# Evaluation_kit.net
KiCad netlist of a schematic drawn in Altium Designer
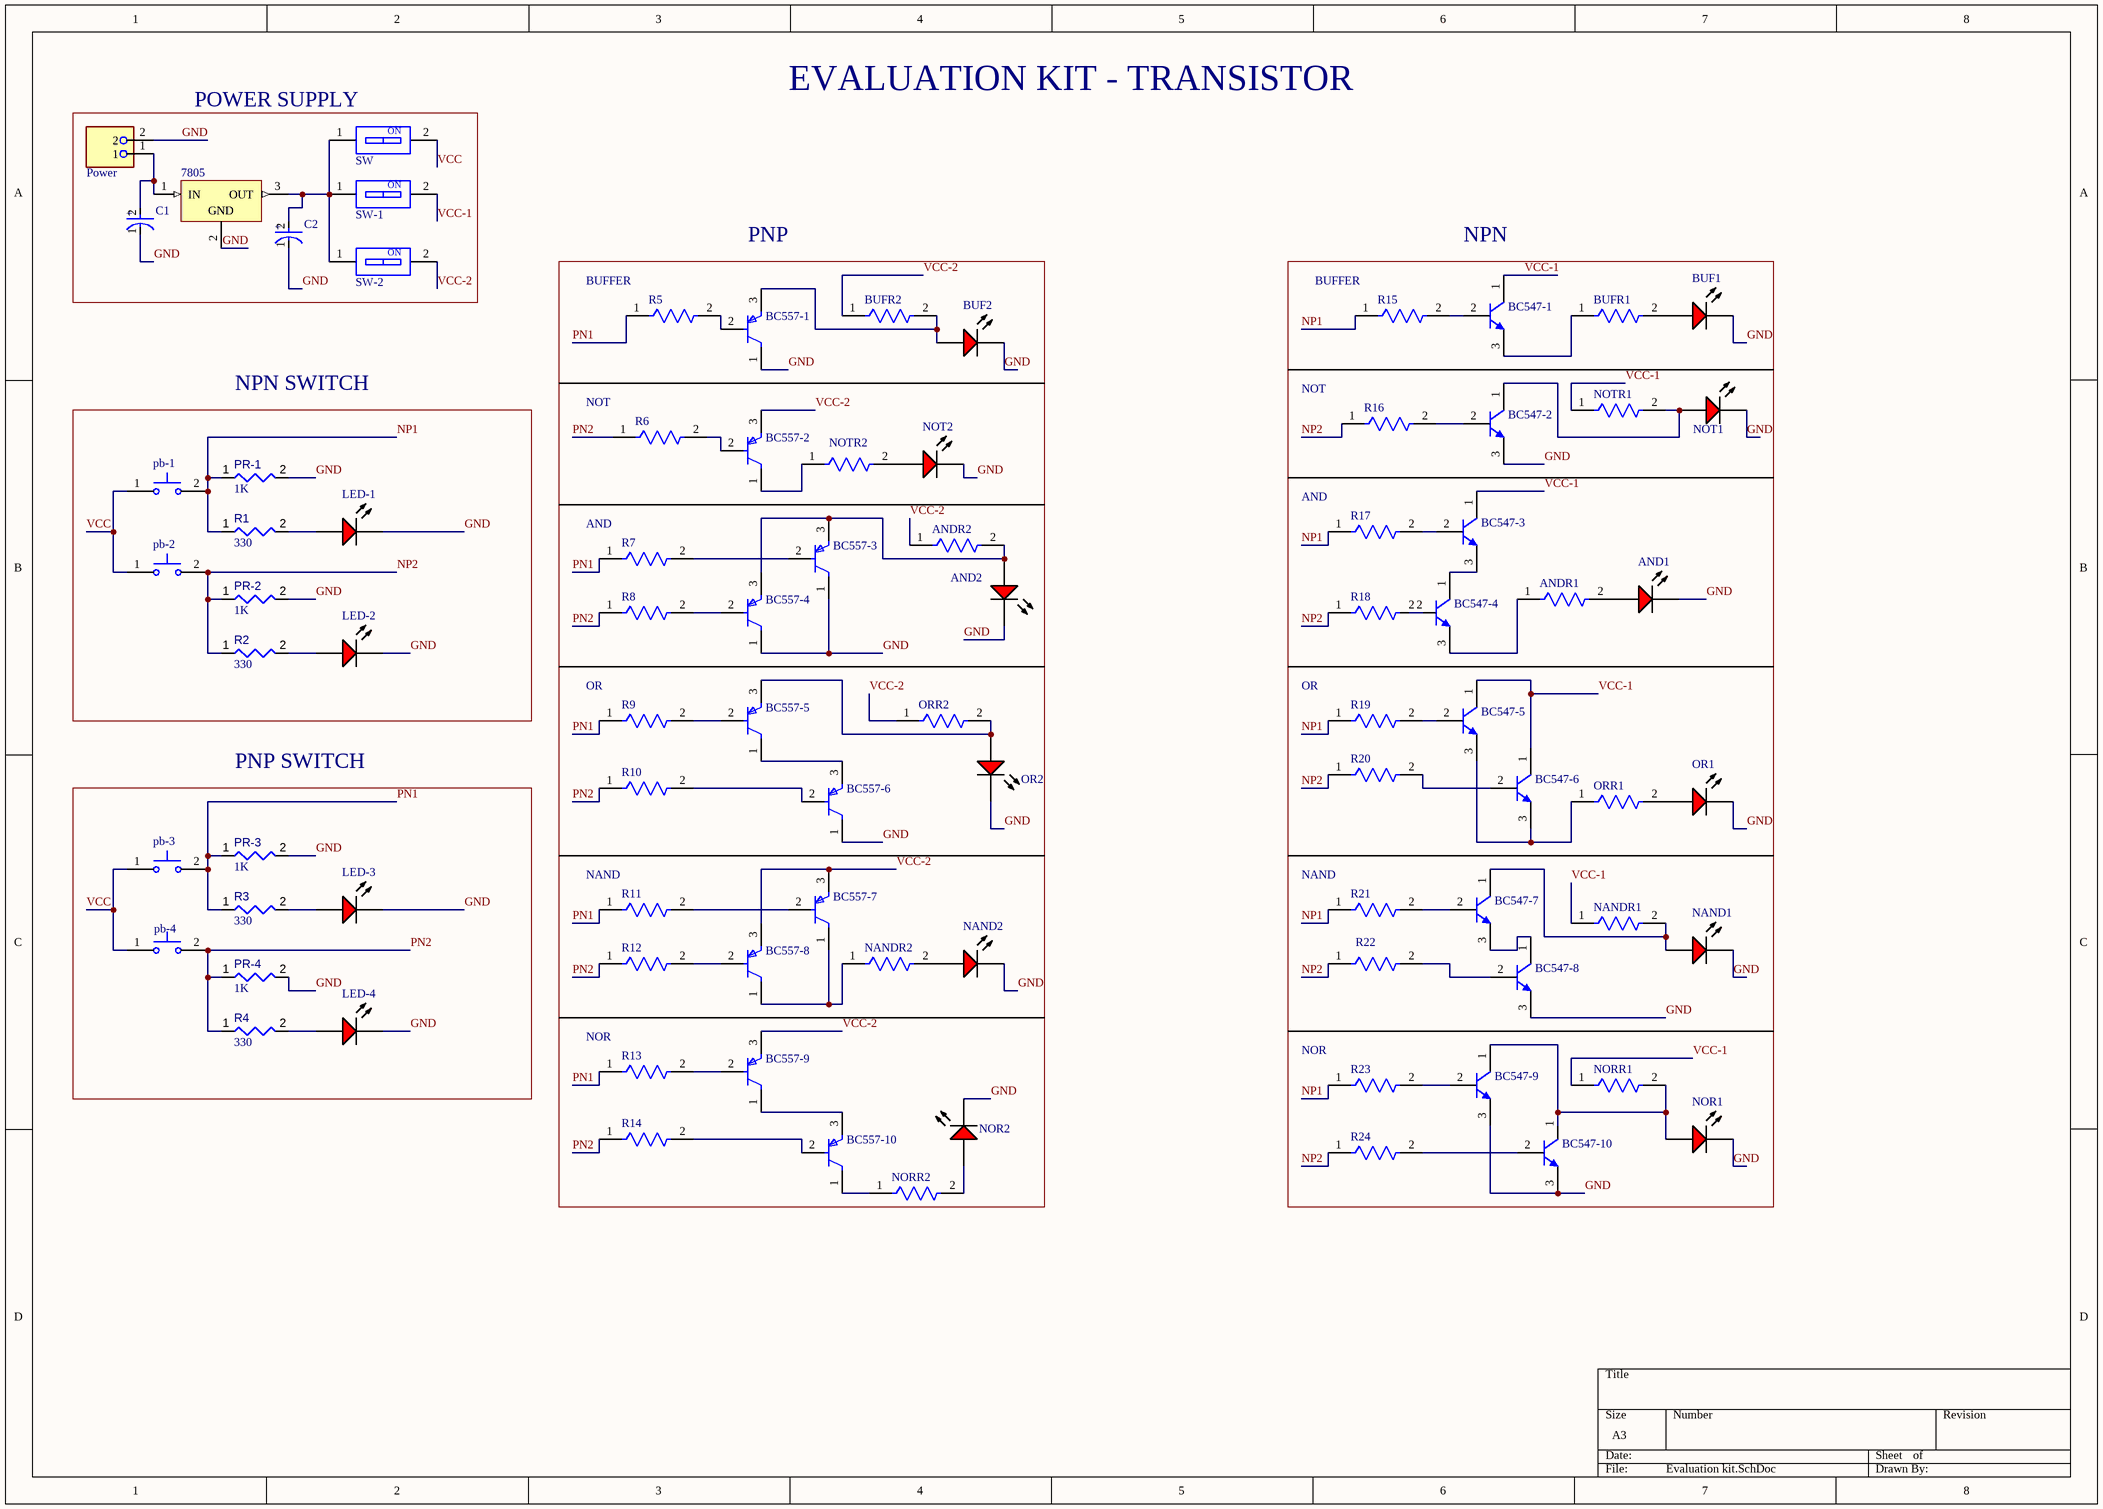
[diagram p0: Evaluation kit.SchDoc]

(export (version "E")
  (design (tool "Eeschema 10.0.6"))
  (components
    (comp (ref "7805")
      (value "LM7805ACT")
      (footprint "FAIR-TO-220-3")
      (description "Positive Voltage Regulator, 5 V, 1 A, 0 to 125 degC, 3-Pin TO-220, RoHS, Tube")
      (fields (field (name "MANUFACTURER") "Fairchild"))
      (libsource (lib "Altium Content Vault") (part "FAIR-LM7805CT-TO220-3"))
    )
    (comp (ref "AND1")
      (value "LTL-1CHE")
      (footprint "INDPR60-254-520X380X650")
      (description "LED Uni-Color Red, 100 mW, 30 mA, -55 to 100 degC, 2-Pin THD, RoHS, Bulk")
      (fields (field (name "MANUFACTURER") "Lite-On"))
      (libsource (lib "KARTHICK RAJ R") (part "LED-RED-AK-2"))
    )
    (comp (ref "AND2")
      (value "LTL-1CHE")
      (footprint "INDPR60-254-520X380X650")
      (description "LED Uni-Color Red, 100 mW, 30 mA, -55 to 100 degC, 2-Pin THD, RoHS, Bulk")
      (fields (field (name "MANUFACTURER") "Lite-On"))
      (libsource (lib "KARTHICK RAJ R") (part "LED-RED-AK-2"))
    )
    (comp (ref "ANDR1")
      (value "MBA02040C2200FC100")
      (footprint "FP-MBA0204-MFG")
      (description "RES 220 OHM 0.4W 1% AXIAL")
      (fields
        (field (name "OCTOPART") "https://octopart.com/mba02040c2200fc100-vishay-43743094")
        (field (name "MANUFACTURER") "Vishay BC Components")
      )
      (libsource (lib "Altium Content Vault") (part "1029c3af85768c4190bb7ad29bc67b5"))
    )
    (comp (ref "ANDR2")
      (value "MBA02040C2200FC100")
      (footprint "FP-MBA0204-MFG")
      (description "RES 220 OHM 0.4W 1% AXIAL")
      (fields
        (field (name "OCTOPART") "https://octopart.com/mba02040c2200fc100-vishay-43743094")
        (field (name "MANUFACTURER") "Vishay BC Components")
      )
      (libsource (lib "Altium Content Vault") (part "1029c3af85768c4190bb7ad29bc67b5"))
    )
    (comp (ref "BC547-1")
      (value "BC547BRL1G")
      (footprint "ONSC-TO-92-3-29-11_AM_BL")
      (description "Amplifier Transistor, NPN Silicon, 3-Pin TO-92, Pb-Free, Tape and Reel")
      (fields (field (name "MANUFACTURER") "On Semiconductor"))
      (libsource (lib "Altium Content Vault") (part "ONSC-NPN-C1B2E3-3"))
    )
    (comp (ref "BC547-2")
      (value "BC547BRL1G")
      (footprint "ONSC-TO-92-3-29-11_AM_BL")
      (description "Amplifier Transistor, NPN Silicon, 3-Pin TO-92, Pb-Free, Tape and Reel")
      (fields (field (name "MANUFACTURER") "On Semiconductor"))
      (libsource (lib "Altium Content Vault") (part "ONSC-NPN-C1B2E3-3"))
    )
    (comp (ref "BC547-3")
      (value "BC547BRL1G")
      (footprint "ONSC-TO-92-3-29-11_AM_BL")
      (description "Amplifier Transistor, NPN Silicon, 3-Pin TO-92, Pb-Free, Tape and Reel")
      (fields (field (name "MANUFACTURER") "On Semiconductor"))
      (libsource (lib "Altium Content Vault") (part "ONSC-NPN-C1B2E3-3"))
    )
    (comp (ref "BC547-4")
      (value "BC547BRL1G")
      (footprint "ONSC-TO-92-3-29-11_AM_BL")
      (description "Amplifier Transistor, NPN Silicon, 3-Pin TO-92, Pb-Free, Tape and Reel")
      (fields (field (name "MANUFACTURER") "On Semiconductor"))
      (libsource (lib "Altium Content Vault") (part "ONSC-NPN-C1B2E3-3"))
    )
    (comp (ref "BC547-5")
      (value "BC547BRL1G")
      (footprint "ONSC-TO-92-3-29-11_AM_BL")
      (description "Amplifier Transistor, NPN Silicon, 3-Pin TO-92, Pb-Free, Tape and Reel")
      (fields (field (name "MANUFACTURER") "On Semiconductor"))
      (libsource (lib "Altium Content Vault") (part "ONSC-NPN-C1B2E3-3"))
    )
    (comp (ref "BC547-6")
      (value "BC547BRL1G")
      (footprint "ONSC-TO-92-3-29-11_AM_BL")
      (description "Amplifier Transistor, NPN Silicon, 3-Pin TO-92, Pb-Free, Tape and Reel")
      (fields (field (name "MANUFACTURER") "On Semiconductor"))
      (libsource (lib "Altium Content Vault") (part "ONSC-NPN-C1B2E3-3"))
    )
    (comp (ref "BC547-7")
      (value "BC547BRL1G")
      (footprint "ONSC-TO-92-3-29-11_AM_BL")
      (description "Amplifier Transistor, NPN Silicon, 3-Pin TO-92, Pb-Free, Tape and Reel")
      (fields (field (name "MANUFACTURER") "On Semiconductor"))
      (libsource (lib "Altium Content Vault") (part "ONSC-NPN-C1B2E3-3"))
    )
    (comp (ref "BC547-8")
      (value "BC547BRL1G")
      (footprint "ONSC-TO-92-3-29-11_AM_BL")
      (description "Amplifier Transistor, NPN Silicon, 3-Pin TO-92, Pb-Free, Tape and Reel")
      (fields (field (name "MANUFACTURER") "On Semiconductor"))
      (libsource (lib "Altium Content Vault") (part "ONSC-NPN-C1B2E3-3"))
    )
    (comp (ref "BC547-9")
      (value "BC547BRL1G")
      (footprint "ONSC-TO-92-3-29-11_AM_BL")
      (description "Amplifier Transistor, NPN Silicon, 3-Pin TO-92, Pb-Free, Tape and Reel")
      (fields (field (name "MANUFACTURER") "On Semiconductor"))
      (libsource (lib "Altium Content Vault") (part "ONSC-NPN-C1B2E3-3"))
    )
    (comp (ref "BC547-10")
      (value "BC547BRL1G")
      (footprint "ONSC-TO-92-3-29-11_AM_BL")
      (description "Amplifier Transistor, NPN Silicon, 3-Pin TO-92, Pb-Free, Tape and Reel")
      (fields (field (name "MANUFACTURER") "On Semiconductor"))
      (libsource (lib "Altium Content Vault") (part "ONSC-NPN-C1B2E3-3"))
    )
    (comp (ref "BC557-1")
      (value "BC557BTF")
      (footprint "FP-135AR-MFG")
      (description "BC557BTF Small Signal Bipolar Transistor, 0.1A I(C), 45V V(BR)CEO, 1-Element, PNP, Silicon, TO-92")
      (libsource (lib "Altium Content Vault") (part "9e2844d3eb996af6824d2c99fe21afc"))
    )
    (comp (ref "BC557-2")
      (value "BC557BTF")
      (footprint "FP-135AR-MFG")
      (description "BC557BTF Small Signal Bipolar Transistor, 0.1A I(C), 45V V(BR)CEO, 1-Element, PNP, Silicon, TO-92")
      (libsource (lib "Altium Content Vault") (part "9e2844d3eb996af6824d2c99fe21afc"))
    )
    (comp (ref "BC557-3")
      (value "BC557BTF")
      (footprint "FP-135AR-MFG")
      (description "BC557BTF Small Signal Bipolar Transistor, 0.1A I(C), 45V V(BR)CEO, 1-Element, PNP, Silicon, TO-92")
      (libsource (lib "Altium Content Vault") (part "9e2844d3eb996af6824d2c99fe21afc"))
    )
    (comp (ref "BC557-4")
      (value "BC557BTF")
      (footprint "FP-135AR-MFG")
      (description "BC557BTF Small Signal Bipolar Transistor, 0.1A I(C), 45V V(BR)CEO, 1-Element, PNP, Silicon, TO-92")
      (libsource (lib "Altium Content Vault") (part "9e2844d3eb996af6824d2c99fe21afc"))
    )
    (comp (ref "BC557-5")
      (value "BC557BTF")
      (footprint "FP-135AR-MFG")
      (description "BC557BTF Small Signal Bipolar Transistor, 0.1A I(C), 45V V(BR)CEO, 1-Element, PNP, Silicon, TO-92")
      (libsource (lib "Altium Content Vault") (part "9e2844d3eb996af6824d2c99fe21afc"))
    )
    (comp (ref "BC557-6")
      (value "BC557BTF")
      (footprint "FP-135AR-MFG")
      (description "BC557BTF Small Signal Bipolar Transistor, 0.1A I(C), 45V V(BR)CEO, 1-Element, PNP, Silicon, TO-92")
      (libsource (lib "Altium Content Vault") (part "9e2844d3eb996af6824d2c99fe21afc"))
    )
    (comp (ref "BC557-7")
      (value "BC557BTF")
      (footprint "FP-135AR-MFG")
      (description "BC557BTF Small Signal Bipolar Transistor, 0.1A I(C), 45V V(BR)CEO, 1-Element, PNP, Silicon, TO-92")
      (libsource (lib "Altium Content Vault") (part "9e2844d3eb996af6824d2c99fe21afc"))
    )
    (comp (ref "BC557-8")
      (value "BC557BTF")
      (footprint "FP-135AR-MFG")
      (description "BC557BTF Small Signal Bipolar Transistor, 0.1A I(C), 45V V(BR)CEO, 1-Element, PNP, Silicon, TO-92")
      (libsource (lib "Altium Content Vault") (part "9e2844d3eb996af6824d2c99fe21afc"))
    )
    (comp (ref "BC557-9")
      (value "BC557BTF")
      (footprint "FP-135AR-MFG")
      (description "BC557BTF Small Signal Bipolar Transistor, 0.1A I(C), 45V V(BR)CEO, 1-Element, PNP, Silicon, TO-92")
      (libsource (lib "Altium Content Vault") (part "9e2844d3eb996af6824d2c99fe21afc"))
    )
    (comp (ref "BC557-10")
      (value "BC557BTF")
      (footprint "FP-135AR-MFG")
      (description "BC557BTF Small Signal Bipolar Transistor, 0.1A I(C), 45V V(BR)CEO, 1-Element, PNP, Silicon, TO-92")
      (libsource (lib "Altium Content Vault") (part "9e2844d3eb996af6824d2c99fe21afc"))
    )
    (comp (ref "BUF1")
      (value "LTL-1CHE")
      (footprint "INDPR60-254-520X380X650")
      (description "LED Uni-Color Red, 100 mW, 30 mA, -55 to 100 degC, 2-Pin THD, RoHS, Bulk")
      (fields (field (name "MANUFACTURER") "Lite-On"))
      (libsource (lib "KARTHICK RAJ R") (part "LED-RED-AK-2"))
    )
    (comp (ref "BUF2")
      (value "LTL-1CHE")
      (footprint "INDPR60-254-520X380X650")
      (description "LED Uni-Color Red, 100 mW, 30 mA, -55 to 100 degC, 2-Pin THD, RoHS, Bulk")
      (fields (field (name "MANUFACTURER") "Lite-On"))
      (libsource (lib "KARTHICK RAJ R") (part "LED-RED-AK-2"))
    )
    (comp (ref "BUFR1")
      (value "MBA02040C2200FC100")
      (footprint "FP-MBA0204-MFG")
      (description "RES 220 OHM 0.4W 1% AXIAL")
      (fields
        (field (name "OCTOPART") "https://octopart.com/mba02040c2200fc100-vishay-43743094")
        (field (name "MANUFACTURER") "Vishay BC Components")
      )
      (libsource (lib "Altium Content Vault") (part "1029c3af85768c4190bb7ad29bc67b5"))
    )
    (comp (ref "BUFR2")
      (value "MBA02040C2200FC100")
      (footprint "FP-MBA0204-MFG")
      (description "RES 220 OHM 0.4W 1% AXIAL")
      (fields
        (field (name "OCTOPART") "https://octopart.com/mba02040c2200fc100-vishay-43743094")
        (field (name "MANUFACTURER") "Vishay BC Components")
      )
      (libsource (lib "Altium Content Vault") (part "1029c3af85768c4190bb7ad29bc67b5"))
    )
    (comp (ref "C1")
      (value "EEU-FR1H101B")
      (footprint "FP-EEU-FR1H101B-MFG")
      (description "CAP ALUM 100UF 20% 50V RADIAL")
      (fields (field (name "TOLERANCE") "20%"))
      (libsource (lib "Altium Content Vault") (part "cf48714ba7e38822c1575c7ec0b6d1f"))
    )
    (comp (ref "C2")
      (value "EEU-FR1H101B")
      (footprint "FP-EEU-FR1H101B-MFG")
      (description "CAP ALUM 100UF 20% 50V RADIAL")
      (fields (field (name "TOLERANCE") "20%"))
      (libsource (lib "Altium Content Vault") (part "cf48714ba7e38822c1575c7ec0b6d1f"))
    )
    (comp (ref "LED-1")
      (value "LTL-1CHE")
      (footprint "INDPR60-254-520X380X650")
      (description "LED Uni-Color Red, 100 mW, 30 mA, -55 to 100 degC, 2-Pin THD, RoHS, Bulk")
      (fields (field (name "MANUFACTURER") "Lite-On"))
      (libsource (lib "KARTHICK RAJ R") (part "LED-RED-AK-2"))
    )
    (comp (ref "LED-2")
      (value "LTL-1CHE")
      (footprint "INDPR60-254-520X380X650")
      (description "LED Uni-Color Red, 100 mW, 30 mA, -55 to 100 degC, 2-Pin THD, RoHS, Bulk")
      (fields (field (name "MANUFACTURER") "Lite-On"))
      (libsource (lib "KARTHICK RAJ R") (part "LED-RED-AK-2"))
    )
    (comp (ref "LED-3")
      (value "LTL-1CHE")
      (footprint "INDPR60-254-520X380X650")
      (description "LED Uni-Color Red, 100 mW, 30 mA, -55 to 100 degC, 2-Pin THD, RoHS, Bulk")
      (fields (field (name "MANUFACTURER") "Lite-On"))
      (libsource (lib "KARTHICK RAJ R") (part "LED-RED-AK-2"))
    )
    (comp (ref "LED-4")
      (value "LTL-1CHE")
      (footprint "INDPR60-254-520X380X650")
      (description "LED Uni-Color Red, 100 mW, 30 mA, -55 to 100 degC, 2-Pin THD, RoHS, Bulk")
      (fields (field (name "MANUFACTURER") "Lite-On"))
      (libsource (lib "KARTHICK RAJ R") (part "LED-RED-AK-2"))
    )
    (comp (ref "NAND1")
      (value "LTL-1CHE")
      (footprint "INDPR60-254-520X380X650")
      (description "LED Uni-Color Red, 100 mW, 30 mA, -55 to 100 degC, 2-Pin THD, RoHS, Bulk")
      (fields (field (name "MANUFACTURER") "Lite-On"))
      (libsource (lib "KARTHICK RAJ R") (part "LED-RED-AK-2"))
    )
    (comp (ref "NAND2")
      (value "LTL-1CHE")
      (footprint "INDPR60-254-520X380X650")
      (description "LED Uni-Color Red, 100 mW, 30 mA, -55 to 100 degC, 2-Pin THD, RoHS, Bulk")
      (fields (field (name "MANUFACTURER") "Lite-On"))
      (libsource (lib "KARTHICK RAJ R") (part "LED-RED-AK-2"))
    )
    (comp (ref "NANDR1")
      (value "MBA02040C2200FC100")
      (footprint "FP-MBA0204-MFG")
      (description "RES 220 OHM 0.4W 1% AXIAL")
      (fields
        (field (name "OCTOPART") "https://octopart.com/mba02040c2200fc100-vishay-43743094")
        (field (name "MANUFACTURER") "Vishay BC Components")
      )
      (libsource (lib "Altium Content Vault") (part "1029c3af85768c4190bb7ad29bc67b5"))
    )
    (comp (ref "NANDR2")
      (value "MBA02040C2200FC100")
      (footprint "FP-MBA0204-MFG")
      (description "RES 220 OHM 0.4W 1% AXIAL")
      (fields
        (field (name "OCTOPART") "https://octopart.com/mba02040c2200fc100-vishay-43743094")
        (field (name "MANUFACTURER") "Vishay BC Components")
      )
      (libsource (lib "Altium Content Vault") (part "1029c3af85768c4190bb7ad29bc67b5"))
    )
    (comp (ref "NOR1")
      (value "LTL-1CHE")
      (footprint "INDPR60-254-520X380X650")
      (description "LED Uni-Color Red, 100 mW, 30 mA, -55 to 100 degC, 2-Pin THD, RoHS, Bulk")
      (fields (field (name "MANUFACTURER") "Lite-On"))
      (libsource (lib "KARTHICK RAJ R") (part "LED-RED-AK-2"))
    )
    (comp (ref "NOR2")
      (value "LTL-1CHE")
      (footprint "INDPR60-254-520X380X650")
      (description "LED Uni-Color Red, 100 mW, 30 mA, -55 to 100 degC, 2-Pin THD, RoHS, Bulk")
      (fields (field (name "MANUFACTURER") "Lite-On"))
      (libsource (lib "KARTHICK RAJ R") (part "LED-RED-AK-2"))
    )
    (comp (ref "NORR1")
      (value "MBA02040C2200FC100")
      (footprint "FP-MBA0204-MFG")
      (description "RES 220 OHM 0.4W 1% AXIAL")
      (fields
        (field (name "OCTOPART") "https://octopart.com/mba02040c2200fc100-vishay-43743094")
        (field (name "MANUFACTURER") "Vishay BC Components")
      )
      (libsource (lib "Altium Content Vault") (part "1029c3af85768c4190bb7ad29bc67b5"))
    )
    (comp (ref "NORR2")
      (value "MBA02040C2200FC100")
      (footprint "FP-MBA0204-MFG")
      (description "RES 220 OHM 0.4W 1% AXIAL")
      (fields
        (field (name "OCTOPART") "https://octopart.com/mba02040c2200fc100-vishay-43743094")
        (field (name "MANUFACTURER") "Vishay BC Components")
      )
      (libsource (lib "Altium Content Vault") (part "1029c3af85768c4190bb7ad29bc67b5"))
    )
    (comp (ref "NOT1")
      (value "LTL-1CHE")
      (footprint "INDPR60-254-520X380X650")
      (description "LED Uni-Color Red, 100 mW, 30 mA, -55 to 100 degC, 2-Pin THD, RoHS, Bulk")
      (fields (field (name "MANUFACTURER") "Lite-On"))
      (libsource (lib "KARTHICK RAJ R") (part "LED-RED-AK-2"))
    )
    (comp (ref "NOT2")
      (value "LTL-1CHE")
      (footprint "INDPR60-254-520X380X650")
      (description "LED Uni-Color Red, 100 mW, 30 mA, -55 to 100 degC, 2-Pin THD, RoHS, Bulk")
      (fields (field (name "MANUFACTURER") "Lite-On"))
      (libsource (lib "KARTHICK RAJ R") (part "LED-RED-AK-2"))
    )
    (comp (ref "NOTR1")
      (value "MBA02040C2200FC100")
      (footprint "FP-MBA0204-MFG")
      (description "RES 220 OHM 0.4W 1% AXIAL")
      (fields
        (field (name "OCTOPART") "https://octopart.com/mba02040c2200fc100-vishay-43743094")
        (field (name "MANUFACTURER") "Vishay BC Components")
      )
      (libsource (lib "Altium Content Vault") (part "1029c3af85768c4190bb7ad29bc67b5"))
    )
    (comp (ref "NOTR2")
      (value "MBA02040C2200FC100")
      (footprint "FP-MBA0204-MFG")
      (description "RES 220 OHM 0.4W 1% AXIAL")
      (fields
        (field (name "OCTOPART") "https://octopart.com/mba02040c2200fc100-vishay-43743094")
        (field (name "MANUFACTURER") "Vishay BC Components")
      )
      (libsource (lib "Altium Content Vault") (part "1029c3af85768c4190bb7ad29bc67b5"))
    )
    (comp (ref "OR1")
      (value "LTL-1CHE")
      (footprint "INDPR60-254-520X380X650")
      (description "LED Uni-Color Red, 100 mW, 30 mA, -55 to 100 degC, 2-Pin THD, RoHS, Bulk")
      (fields (field (name "MANUFACTURER") "Lite-On"))
      (libsource (lib "KARTHICK RAJ R") (part "LED-RED-AK-2"))
    )
    (comp (ref "OR2")
      (value "LTL-1CHE")
      (footprint "INDPR60-254-520X380X650")
      (description "LED Uni-Color Red, 100 mW, 30 mA, -55 to 100 degC, 2-Pin THD, RoHS, Bulk")
      (fields (field (name "MANUFACTURER") "Lite-On"))
      (libsource (lib "KARTHICK RAJ R") (part "LED-RED-AK-2"))
    )
    (comp (ref "ORR1")
      (value "MBA02040C2200FC100")
      (footprint "FP-MBA0204-MFG")
      (description "RES 220 OHM 0.4W 1% AXIAL")
      (fields
        (field (name "OCTOPART") "https://octopart.com/mba02040c2200fc100-vishay-43743094")
        (field (name "MANUFACTURER") "Vishay BC Components")
      )
      (libsource (lib "Altium Content Vault") (part "1029c3af85768c4190bb7ad29bc67b5"))
    )
    (comp (ref "ORR2")
      (value "MBA02040C2200FC100")
      (footprint "FP-MBA0204-MFG")
      (description "RES 220 OHM 0.4W 1% AXIAL")
      (fields
        (field (name "OCTOPART") "https://octopart.com/mba02040c2200fc100-vishay-43743094")
        (field (name "MANUFACTURER") "Vishay BC Components")
      )
      (libsource (lib "Altium Content Vault") (part "1029c3af85768c4190bb7ad29bc67b5"))
    )
    (comp (ref "pb-1")
      (value "BUTT-2")
      (footprint "SW_BUTT-2")
      (description "Tactile Switches MINI PUSH BUTTON SWITCH 2-PIN QTY. 4")
      (fields (field (name "MF") "Gravitech"))
      (libsource (lib "BUTT-2") (part "BUTT-2"))
    )
    (comp (ref "pb-2")
      (value "BUTT-2")
      (footprint "SW_BUTT-2")
      (description "Tactile Switches MINI PUSH BUTTON SWITCH 2-PIN QTY. 4")
      (fields (field (name "MF") "Gravitech"))
      (libsource (lib "BUTT-2") (part "BUTT-2"))
    )
    (comp (ref "pb-3")
      (value "BUTT-2")
      (footprint "SW_BUTT-2")
      (description "Tactile Switches MINI PUSH BUTTON SWITCH 2-PIN QTY. 4")
      (fields (field (name "MF") "Gravitech"))
      (libsource (lib "BUTT-2") (part "BUTT-2"))
    )
    (comp (ref "pb-4")
      (value "BUTT-2")
      (footprint "SW_BUTT-2")
      (description "Tactile Switches MINI PUSH BUTTON SWITCH 2-PIN QTY. 4")
      (fields (field (name "MF") "Gravitech"))
      (libsource (lib "BUTT-2") (part "BUTT-2"))
    )
    (comp (ref "Power")
      (value "1729128")
      (footprint "PHOENIX_1729128")
      (fields (field (name "MF") "Phoenix Contact"))
      (libsource (lib "1729128") (part "1729128"))
    )
    (comp (ref "PR-1")
      (value "1K")
      (footprint "RESA60-630X240")
      (description "Axial Resistor, 100 Ohm, +/- 1%, 0.25 W, -55 to 155 degC, 2-Pin THD, RoHS, Bulk")
      (fields (field (name "MANUFACTURER") "Yageo") (field (name "TOLERANCE") "1%"))
      (libsource (lib "KARTHICK RAJ R") (part "RES-2"))
    )
    (comp (ref "PR-2")
      (value "1K")
      (footprint "RESA60-630X240")
      (description "Axial Resistor, 100 Ohm, +/- 1%, 0.25 W, -55 to 155 degC, 2-Pin THD, RoHS, Bulk")
      (fields (field (name "MANUFACTURER") "Yageo") (field (name "TOLERANCE") "1%"))
      (libsource (lib "KARTHICK RAJ R") (part "RES-2"))
    )
    (comp (ref "PR-3")
      (value "1K")
      (footprint "RESA60-630X240")
      (description "Axial Resistor, 100 Ohm, +/- 1%, 0.25 W, -55 to 155 degC, 2-Pin THD, RoHS, Bulk")
      (fields (field (name "MANUFACTURER") "Yageo") (field (name "TOLERANCE") "1%"))
      (libsource (lib "KARTHICK RAJ R") (part "RES-2"))
    )
    (comp (ref "PR-4")
      (value "1K")
      (footprint "RESA60-630X240")
      (description "Axial Resistor, 100 Ohm, +/- 1%, 0.25 W, -55 to 155 degC, 2-Pin THD, RoHS, Bulk")
      (fields (field (name "MANUFACTURER") "Yageo") (field (name "TOLERANCE") "1%"))
      (libsource (lib "KARTHICK RAJ R") (part "RES-2"))
    )
    (comp (ref "R1")
      (value "330")
      (footprint "RESA60-630X240")
      (description "Axial Resistor, 100 Ohm, +/- 1%, 0.25 W, -55 to 155 degC, 2-Pin THD, RoHS, Bulk")
      (fields (field (name "MANUFACTURER") "Yageo") (field (name "TOLERANCE") "1%"))
      (libsource (lib "KARTHICK RAJ R") (part "RES-2"))
    )
    (comp (ref "R2")
      (value "330")
      (footprint "RESA60-630X240")
      (description "Axial Resistor, 100 Ohm, +/- 1%, 0.25 W, -55 to 155 degC, 2-Pin THD, RoHS, Bulk")
      (fields (field (name "MANUFACTURER") "Yageo") (field (name "TOLERANCE") "1%"))
      (libsource (lib "KARTHICK RAJ R") (part "RES-2"))
    )
    (comp (ref "R3")
      (value "330")
      (footprint "RESA60-630X240")
      (description "Axial Resistor, 100 Ohm, +/- 1%, 0.25 W, -55 to 155 degC, 2-Pin THD, RoHS, Bulk")
      (fields (field (name "MANUFACTURER") "Yageo") (field (name "TOLERANCE") "1%"))
      (libsource (lib "KARTHICK RAJ R") (part "RES-2"))
    )
    (comp (ref "R4")
      (value "330")
      (footprint "RESA60-630X240")
      (description "Axial Resistor, 100 Ohm, +/- 1%, 0.25 W, -55 to 155 degC, 2-Pin THD, RoHS, Bulk")
      (fields (field (name "MANUFACTURER") "Yageo") (field (name "TOLERANCE") "1%"))
      (libsource (lib "KARTHICK RAJ R") (part "RES-2"))
    )
    (comp (ref "R5")
      (value "MBA02040C2200FC100")
      (footprint "FP-MBA0204-MFG")
      (description "RES 220 OHM 0.4W 1% AXIAL")
      (fields
        (field (name "OCTOPART") "https://octopart.com/mba02040c2200fc100-vishay-43743094")
        (field (name "MANUFACTURER") "Vishay BC Components")
      )
      (libsource (lib "Altium Content Vault") (part "1029c3af85768c4190bb7ad29bc67b5"))
    )
    (comp (ref "R6")
      (value "MBA02040C2200FC100")
      (footprint "FP-MBA0204-MFG")
      (description "RES 220 OHM 0.4W 1% AXIAL")
      (fields
        (field (name "OCTOPART") "https://octopart.com/mba02040c2200fc100-vishay-43743094")
        (field (name "MANUFACTURER") "Vishay BC Components")
      )
      (libsource (lib "Altium Content Vault") (part "1029c3af85768c4190bb7ad29bc67b5"))
    )
    (comp (ref "R7")
      (value "MBA02040C2200FC100")
      (footprint "FP-MBA0204-MFG")
      (description "RES 220 OHM 0.4W 1% AXIAL")
      (fields
        (field (name "OCTOPART") "https://octopart.com/mba02040c2200fc100-vishay-43743094")
        (field (name "MANUFACTURER") "Vishay BC Components")
      )
      (libsource (lib "Altium Content Vault") (part "1029c3af85768c4190bb7ad29bc67b5"))
    )
    (comp (ref "R8")
      (value "MBA02040C2200FC100")
      (footprint "FP-MBA0204-MFG")
      (description "RES 220 OHM 0.4W 1% AXIAL")
      (fields
        (field (name "OCTOPART") "https://octopart.com/mba02040c2200fc100-vishay-43743094")
        (field (name "MANUFACTURER") "Vishay BC Components")
      )
      (libsource (lib "Altium Content Vault") (part "1029c3af85768c4190bb7ad29bc67b5"))
    )
    (comp (ref "R9")
      (value "MBA02040C2200FC100")
      (footprint "FP-MBA0204-MFG")
      (description "RES 220 OHM 0.4W 1% AXIAL")
      (fields
        (field (name "OCTOPART") "https://octopart.com/mba02040c2200fc100-vishay-43743094")
        (field (name "MANUFACTURER") "Vishay BC Components")
      )
      (libsource (lib "Altium Content Vault") (part "1029c3af85768c4190bb7ad29bc67b5"))
    )
    (comp (ref "R10")
      (value "MBA02040C2200FC100")
      (footprint "FP-MBA0204-MFG")
      (description "RES 220 OHM 0.4W 1% AXIAL")
      (fields
        (field (name "OCTOPART") "https://octopart.com/mba02040c2200fc100-vishay-43743094")
        (field (name "MANUFACTURER") "Vishay BC Components")
      )
      (libsource (lib "Altium Content Vault") (part "1029c3af85768c4190bb7ad29bc67b5"))
    )
    (comp (ref "R11")
      (value "MBA02040C2200FC100")
      (footprint "FP-MBA0204-MFG")
      (description "RES 220 OHM 0.4W 1% AXIAL")
      (fields
        (field (name "OCTOPART") "https://octopart.com/mba02040c2200fc100-vishay-43743094")
        (field (name "MANUFACTURER") "Vishay BC Components")
      )
      (libsource (lib "Altium Content Vault") (part "1029c3af85768c4190bb7ad29bc67b5"))
    )
    (comp (ref "R12")
      (value "MBA02040C2200FC100")
      (footprint "FP-MBA0204-MFG")
      (description "RES 220 OHM 0.4W 1% AXIAL")
      (fields
        (field (name "OCTOPART") "https://octopart.com/mba02040c2200fc100-vishay-43743094")
        (field (name "MANUFACTURER") "Vishay BC Components")
      )
      (libsource (lib "Altium Content Vault") (part "1029c3af85768c4190bb7ad29bc67b5"))
    )
    (comp (ref "R13")
      (value "MBA02040C2200FC100")
      (footprint "FP-MBA0204-MFG")
      (description "RES 220 OHM 0.4W 1% AXIAL")
      (fields
        (field (name "OCTOPART") "https://octopart.com/mba02040c2200fc100-vishay-43743094")
        (field (name "MANUFACTURER") "Vishay BC Components")
      )
      (libsource (lib "Altium Content Vault") (part "1029c3af85768c4190bb7ad29bc67b5"))
    )
    (comp (ref "R14")
      (value "MBA02040C2200FC100")
      (footprint "FP-MBA0204-MFG")
      (description "RES 220 OHM 0.4W 1% AXIAL")
      (fields
        (field (name "OCTOPART") "https://octopart.com/mba02040c2200fc100-vishay-43743094")
        (field (name "MANUFACTURER") "Vishay BC Components")
      )
      (libsource (lib "Altium Content Vault") (part "1029c3af85768c4190bb7ad29bc67b5"))
    )
    (comp (ref "R15")
      (value "MBA02040C2200FC100")
      (footprint "FP-MBA0204-MFG")
      (description "RES 220 OHM 0.4W 1% AXIAL")
      (fields
        (field (name "OCTOPART") "https://octopart.com/mba02040c2200fc100-vishay-43743094")
        (field (name "MANUFACTURER") "Vishay BC Components")
      )
      (libsource (lib "Altium Content Vault") (part "1029c3af85768c4190bb7ad29bc67b5"))
    )
    (comp (ref "R16")
      (value "MBA02040C2200FC100")
      (footprint "FP-MBA0204-MFG")
      (description "RES 220 OHM 0.4W 1% AXIAL")
      (fields
        (field (name "OCTOPART") "https://octopart.com/mba02040c2200fc100-vishay-43743094")
        (field (name "MANUFACTURER") "Vishay BC Components")
      )
      (libsource (lib "Altium Content Vault") (part "1029c3af85768c4190bb7ad29bc67b5"))
    )
    (comp (ref "R17")
      (value "MBA02040C2200FC100")
      (footprint "FP-MBA0204-MFG")
      (description "RES 220 OHM 0.4W 1% AXIAL")
      (fields
        (field (name "OCTOPART") "https://octopart.com/mba02040c2200fc100-vishay-43743094")
        (field (name "MANUFACTURER") "Vishay BC Components")
      )
      (libsource (lib "Altium Content Vault") (part "1029c3af85768c4190bb7ad29bc67b5"))
    )
    (comp (ref "R18")
      (value "MBA02040C2200FC100")
      (footprint "FP-MBA0204-MFG")
      (description "RES 220 OHM 0.4W 1% AXIAL")
      (fields
        (field (name "OCTOPART") "https://octopart.com/mba02040c2200fc100-vishay-43743094")
        (field (name "MANUFACTURER") "Vishay BC Components")
      )
      (libsource (lib "Altium Content Vault") (part "1029c3af85768c4190bb7ad29bc67b5"))
    )
    (comp (ref "R19")
      (value "MBA02040C2200FC100")
      (footprint "FP-MBA0204-MFG")
      (description "RES 220 OHM 0.4W 1% AXIAL")
      (fields
        (field (name "OCTOPART") "https://octopart.com/mba02040c2200fc100-vishay-43743094")
        (field (name "MANUFACTURER") "Vishay BC Components")
      )
      (libsource (lib "Altium Content Vault") (part "1029c3af85768c4190bb7ad29bc67b5"))
    )
    (comp (ref "R20")
      (value "MBA02040C2200FC100")
      (footprint "FP-MBA0204-MFG")
      (description "RES 220 OHM 0.4W 1% AXIAL")
      (fields
        (field (name "OCTOPART") "https://octopart.com/mba02040c2200fc100-vishay-43743094")
        (field (name "MANUFACTURER") "Vishay BC Components")
      )
      (libsource (lib "Altium Content Vault") (part "1029c3af85768c4190bb7ad29bc67b5"))
    )
    (comp (ref "R21")
      (value "MBA02040C2200FC100")
      (footprint "FP-MBA0204-MFG")
      (description "RES 220 OHM 0.4W 1% AXIAL")
      (fields
        (field (name "OCTOPART") "https://octopart.com/mba02040c2200fc100-vishay-43743094")
        (field (name "MANUFACTURER") "Vishay BC Components")
      )
      (libsource (lib "Altium Content Vault") (part "1029c3af85768c4190bb7ad29bc67b5"))
    )
    (comp (ref "R22")
      (value "MBA02040C2200FC100")
      (footprint "FP-MBA0204-MFG")
      (description "RES 220 OHM 0.4W 1% AXIAL")
      (fields
        (field (name "OCTOPART") "https://octopart.com/mba02040c2200fc100-vishay-43743094")
        (field (name "MANUFACTURER") "Vishay BC Components")
      )
      (libsource (lib "Altium Content Vault") (part "1029c3af85768c4190bb7ad29bc67b5"))
    )
    (comp (ref "R23")
      (value "MBA02040C2200FC100")
      (footprint "FP-MBA0204-MFG")
      (description "RES 220 OHM 0.4W 1% AXIAL")
      (fields
        (field (name "OCTOPART") "https://octopart.com/mba02040c2200fc100-vishay-43743094")
        (field (name "MANUFACTURER") "Vishay BC Components")
      )
      (libsource (lib "Altium Content Vault") (part "1029c3af85768c4190bb7ad29bc67b5"))
    )
    (comp (ref "R24")
      (value "MBA02040C2200FC100")
      (footprint "FP-MBA0204-MFG")
      (description "RES 220 OHM 0.4W 1% AXIAL")
      (fields
        (field (name "OCTOPART") "https://octopart.com/mba02040c2200fc100-vishay-43743094")
        (field (name "MANUFACTURER") "Vishay BC Components")
      )
      (libsource (lib "Altium Content Vault") (part "1029c3af85768c4190bb7ad29bc67b5"))
    )
    (comp (ref "SW")
      (value "418117170901")
      (footprint "418117170901")
      (description "WS-DITV Compact THT Dip Switch, Flat Actuator, pitch 2.54mm, 1p")
      (fields (field (name "MANUFACTURER") "Wurth Elektronik"))
      (libsource (lib "Altium_WS-DITV+(rev22a)") (part "418117170901"))
    )
    (comp (ref "SW-1")
      (value "418117170901")
      (footprint "418117170901")
      (description "WS-DITV Compact THT Dip Switch, Flat Actuator, pitch 2.54mm, 1p")
      (fields (field (name "MANUFACTURER") "Wurth Elektronik"))
      (libsource (lib "Altium_WS-DITV+(rev22a)") (part "418117170901"))
    )
    (comp (ref "SW-2")
      (value "418117170901")
      (footprint "418117170901")
      (description "WS-DITV Compact THT Dip Switch, Flat Actuator, pitch 2.54mm, 1p")
      (fields (field (name "MANUFACTURER") "Wurth Elektronik"))
      (libsource (lib "Altium_WS-DITV+(rev22a)") (part "418117170901"))
    )
  )
  (nets
    (net (code "1") (name "/GND") (class "Default")
      (node (ref "7805") (pin "2") (pinfunction "GND_2") (pintype "power_in"))
      (node (ref "AND1") (pin "2") (pinfunction "K_2") (pintype "passive"))
      (node (ref "AND2") (pin "2") (pinfunction "K_2") (pintype "passive"))
      (node (ref "BC547-10") (pin "3") (pinfunction "E_3") (pintype "passive"))
      (node (ref "BC547-2") (pin "3") (pinfunction "E_3") (pintype "passive"))
      (node (ref "BC547-8") (pin "3") (pinfunction "E_3") (pintype "passive"))
      (node (ref "BC547-9") (pin "3") (pinfunction "E_3") (pintype "passive"))
      (node (ref "BC557-1") (pin "1") (pinfunction "C_1") (pintype "passive"))
      (node (ref "BC557-3") (pin "1") (pinfunction "C_1") (pintype "passive"))
      (node (ref "BC557-4") (pin "1") (pinfunction "C_1") (pintype "passive"))
      (node (ref "BC557-6") (pin "1") (pinfunction "C_1") (pintype "passive"))
      (node (ref "BUF1") (pin "2") (pinfunction "K_2") (pintype "passive"))
      (node (ref "BUF2") (pin "2") (pinfunction "K_2") (pintype "passive"))
      (node (ref "C1") (pin "1") (pinfunction "C_1") (pintype "passive"))
      (node (ref "C2") (pin "1") (pinfunction "C_1") (pintype "passive"))
      (node (ref "LED-1") (pin "2") (pinfunction "K_2") (pintype "passive"))
      (node (ref "LED-2") (pin "2") (pinfunction "K_2") (pintype "passive"))
      (node (ref "LED-3") (pin "2") (pinfunction "K_2") (pintype "passive"))
      (node (ref "LED-4") (pin "2") (pinfunction "K_2") (pintype "passive"))
      (node (ref "NAND1") (pin "2") (pinfunction "K_2") (pintype "passive"))
      (node (ref "NAND2") (pin "2") (pinfunction "K_2") (pintype "passive"))
      (node (ref "NOR1") (pin "2") (pinfunction "K_2") (pintype "passive"))
      (node (ref "NOR2") (pin "2") (pinfunction "K_2") (pintype "passive"))
      (node (ref "NOT1") (pin "2") (pinfunction "K_2") (pintype "passive"))
      (node (ref "NOT2") (pin "2") (pinfunction "K_2") (pintype "passive"))
      (node (ref "OR1") (pin "2") (pinfunction "K_2") (pintype "passive"))
      (node (ref "OR2") (pin "2") (pinfunction "K_2") (pintype "passive"))
      (node (ref "PR-1") (pin "2") (pinfunction "2_2") (pintype "passive"))
      (node (ref "PR-2") (pin "2") (pinfunction "2_2") (pintype "passive"))
      (node (ref "PR-3") (pin "2") (pinfunction "2_2") (pintype "passive"))
      (node (ref "PR-4") (pin "2") (pinfunction "2_2") (pintype "passive"))
      (node (ref "Power") (pin "2") (pinfunction "2_2") (pintype "passive"))
    )
    (net (code "2") (name "/NP1") (class "Default")
      (node (ref "PR-1") (pin "1") (pinfunction "1_1") (pintype "passive"))
      (node (ref "R1") (pin "1") (pinfunction "1_1") (pintype "passive"))
      (node (ref "R15") (pin "1") (pinfunction "1_1") (pintype "passive"))
      (node (ref "R17") (pin "1") (pinfunction "1_1") (pintype "passive"))
      (node (ref "R19") (pin "1") (pinfunction "1_1") (pintype "passive"))
      (node (ref "R21") (pin "1") (pinfunction "1_1") (pintype "passive"))
      (node (ref "R23") (pin "1") (pinfunction "1_1") (pintype "passive"))
      (node (ref "pb-1") (pin "2") (pinfunction "2_2") (pintype "passive"))
    )
    (net (code "3") (name "/NP2") (class "Default")
      (node (ref "PR-2") (pin "1") (pinfunction "1_1") (pintype "passive"))
      (node (ref "R16") (pin "1") (pinfunction "1_1") (pintype "passive"))
      (node (ref "R18") (pin "1") (pinfunction "1_1") (pintype "passive"))
      (node (ref "R2") (pin "1") (pinfunction "1_1") (pintype "passive"))
      (node (ref "R20") (pin "1") (pinfunction "1_1") (pintype "passive"))
      (node (ref "R22") (pin "1") (pinfunction "1_1") (pintype "passive"))
      (node (ref "R24") (pin "1") (pinfunction "1_1") (pintype "passive"))
      (node (ref "pb-2") (pin "2") (pinfunction "2_2") (pintype "passive"))
    )
    (net (code "4") (name "/PN1") (class "Default")
      (node (ref "PR-3") (pin "1") (pinfunction "1_1") (pintype "passive"))
      (node (ref "R11") (pin "1") (pinfunction "1_1") (pintype "passive"))
      (node (ref "R13") (pin "1") (pinfunction "1_1") (pintype "passive"))
      (node (ref "R3") (pin "1") (pinfunction "1_1") (pintype "passive"))
      (node (ref "R5") (pin "1") (pinfunction "1_1") (pintype "passive"))
      (node (ref "R7") (pin "1") (pinfunction "1_1") (pintype "passive"))
      (node (ref "R9") (pin "1") (pinfunction "1_1") (pintype "passive"))
      (node (ref "pb-3") (pin "2") (pinfunction "2_2") (pintype "passive"))
    )
    (net (code "5") (name "/PN2") (class "Default")
      (node (ref "PR-4") (pin "1") (pinfunction "1_1") (pintype "passive"))
      (node (ref "R10") (pin "1") (pinfunction "1_1") (pintype "passive"))
      (node (ref "R12") (pin "1") (pinfunction "1_1") (pintype "passive"))
      (node (ref "R14") (pin "1") (pinfunction "1_1") (pintype "passive"))
      (node (ref "R4") (pin "1") (pinfunction "1_1") (pintype "passive"))
      (node (ref "R6") (pin "1") (pinfunction "1_1") (pintype "passive"))
      (node (ref "R8") (pin "1") (pinfunction "1_1") (pintype "passive"))
      (node (ref "pb-4") (pin "2") (pinfunction "2_2") (pintype "passive"))
    )
    (net (code "6") (name "/VCC") (class "Default")
      (node (ref "SW") (pin "2") (pinfunction "2_2") (pintype "passive"))
      (node (ref "pb-1") (pin "1") (pinfunction "1_1") (pintype "passive"))
      (node (ref "pb-2") (pin "1") (pinfunction "1_1") (pintype "passive"))
      (node (ref "pb-3") (pin "1") (pinfunction "1_1") (pintype "passive"))
      (node (ref "pb-4") (pin "1") (pinfunction "1_1") (pintype "passive"))
    )
    (net (code "7") (name "/VCC-1") (class "Default")
      (node (ref "BC547-1") (pin "1") (pinfunction "C_1") (pintype "passive"))
      (node (ref "BC547-3") (pin "1") (pinfunction "C_1") (pintype "passive"))
      (node (ref "BC547-5") (pin "1") (pinfunction "C_1") (pintype "passive"))
      (node (ref "BC547-6") (pin "1") (pinfunction "C_1") (pintype "passive"))
      (node (ref "NANDR1") (pin "1") (pinfunction "1_1") (pintype "passive"))
      (node (ref "NORR1") (pin "1") (pinfunction "1_1") (pintype "passive"))
      (node (ref "NOTR1") (pin "1") (pinfunction "1_1") (pintype "passive"))
      (node (ref "SW-1") (pin "2") (pinfunction "2_2") (pintype "passive"))
    )
    (net (code "8") (name "/VCC-2") (class "Default")
      (node (ref "ANDR2") (pin "1") (pinfunction "1_1") (pintype "passive"))
      (node (ref "BC557-2") (pin "3") (pinfunction "E_3") (pintype "passive"))
      (node (ref "BC557-7") (pin "3") (pinfunction "E_3") (pintype "passive"))
      (node (ref "BC557-8") (pin "3") (pinfunction "E_3") (pintype "passive"))
      (node (ref "BC557-9") (pin "3") (pinfunction "E_3") (pintype "passive"))
      (node (ref "BUFR2") (pin "1") (pinfunction "1_1") (pintype "passive"))
      (node (ref "ORR2") (pin "1") (pinfunction "1_1") (pintype "passive"))
      (node (ref "SW-2") (pin "2") (pinfunction "2_2") (pintype "passive"))
    )
    (net (code "9") (name "Net-(7805-IN)") (class "Default")
      (node (ref "7805") (pin "1") (pinfunction "IN_1") (pintype "input"))
      (node (ref "C1") (pin "2") (pinfunction "A_2") (pintype "passive"))
      (node (ref "Power") (pin "1") (pinfunction "1_1") (pintype "passive"))
    )
    (net (code "10") (name "Net-(7805-OUT)") (class "Default")
      (node (ref "7805") (pin "3") (pinfunction "OUT_3") (pintype "output"))
      (node (ref "C2") (pin "2") (pinfunction "A_2") (pintype "passive"))
      (node (ref "SW") (pin "1") (pinfunction "1_1") (pintype "passive"))
      (node (ref "SW-1") (pin "1") (pinfunction "1_1") (pintype "passive"))
      (node (ref "SW-2") (pin "1") (pinfunction "1_1") (pintype "passive"))
    )
    (net (code "11") (name "Net-(AND1-A)") (class "Default")
      (node (ref "AND1") (pin "1") (pinfunction "A_1") (pintype "passive"))
      (node (ref "ANDR1") (pin "2") (pinfunction "2_2") (pintype "passive"))
    )
    (net (code "12") (name "Net-(AND2-A)") (class "Default")
      (node (ref "AND2") (pin "1") (pinfunction "A_1") (pintype "passive"))
      (node (ref "ANDR2") (pin "2") (pinfunction "2_2") (pintype "passive"))
      (node (ref "BC557-3") (pin "3") (pinfunction "E_3") (pintype "passive"))
      (node (ref "BC557-4") (pin "3") (pinfunction "E_3") (pintype "passive"))
    )
    (net (code "13") (name "Net-(BC547-1-B)") (class "Default")
      (node (ref "BC547-1") (pin "2") (pinfunction "B_2") (pintype "passive"))
      (node (ref "R15") (pin "2") (pinfunction "2_2") (pintype "passive"))
    )
    (net (code "14") (name "Net-(BC547-1-E)") (class "Default")
      (node (ref "BC547-1") (pin "3") (pinfunction "E_3") (pintype "passive"))
      (node (ref "BUFR1") (pin "1") (pinfunction "1_1") (pintype "passive"))
    )
    (net (code "15") (name "Net-(BC547-2-B)") (class "Default")
      (node (ref "BC547-2") (pin "2") (pinfunction "B_2") (pintype "passive"))
      (node (ref "R16") (pin "2") (pinfunction "2_2") (pintype "passive"))
    )
    (net (code "16") (name "Net-(BC547-2-C)") (class "Default")
      (node (ref "BC547-2") (pin "1") (pinfunction "C_1") (pintype "passive"))
      (node (ref "NOT1") (pin "1") (pinfunction "A_1") (pintype "passive"))
      (node (ref "NOTR1") (pin "2") (pinfunction "2_2") (pintype "passive"))
    )
    (net (code "17") (name "Net-(BC547-3-B)") (class "Default")
      (node (ref "BC547-3") (pin "2") (pinfunction "B_2") (pintype "passive"))
      (node (ref "R17") (pin "2") (pinfunction "2_2") (pintype "passive"))
    )
    (net (code "18") (name "Net-(BC547-3-E)") (class "Default")
      (node (ref "BC547-3") (pin "3") (pinfunction "E_3") (pintype "passive"))
      (node (ref "BC547-4") (pin "1") (pinfunction "C_1") (pintype "passive"))
    )
    (net (code "19") (name "Net-(BC547-4-B)") (class "Default")
      (node (ref "BC547-4") (pin "2") (pinfunction "B_2") (pintype "passive"))
      (node (ref "R18") (pin "2") (pinfunction "2_2") (pintype "passive"))
    )
    (net (code "20") (name "Net-(BC547-4-E)") (class "Default")
      (node (ref "ANDR1") (pin "1") (pinfunction "1_1") (pintype "passive"))
      (node (ref "BC547-4") (pin "3") (pinfunction "E_3") (pintype "passive"))
    )
    (net (code "21") (name "Net-(BC547-5-B)") (class "Default")
      (node (ref "BC547-5") (pin "2") (pinfunction "B_2") (pintype "passive"))
      (node (ref "R19") (pin "2") (pinfunction "2_2") (pintype "passive"))
    )
    (net (code "22") (name "Net-(BC547-5-E)") (class "Default")
      (node (ref "BC547-5") (pin "3") (pinfunction "E_3") (pintype "passive"))
      (node (ref "BC547-6") (pin "3") (pinfunction "E_3") (pintype "passive"))
      (node (ref "ORR1") (pin "1") (pinfunction "1_1") (pintype "passive"))
    )
    (net (code "23") (name "Net-(BC547-6-B)") (class "Default")
      (node (ref "BC547-6") (pin "2") (pinfunction "B_2") (pintype "passive"))
      (node (ref "R20") (pin "2") (pinfunction "2_2") (pintype "passive"))
    )
    (net (code "24") (name "Net-(BC547-7-B)") (class "Default")
      (node (ref "BC547-7") (pin "2") (pinfunction "B_2") (pintype "passive"))
      (node (ref "R21") (pin "2") (pinfunction "2_2") (pintype "passive"))
    )
    (net (code "25") (name "Net-(BC547-7-C)") (class "Default")
      (node (ref "BC547-7") (pin "1") (pinfunction "C_1") (pintype "passive"))
      (node (ref "NAND1") (pin "1") (pinfunction "A_1") (pintype "passive"))
      (node (ref "NANDR1") (pin "2") (pinfunction "2_2") (pintype "passive"))
    )
    (net (code "26") (name "Net-(BC547-7-E)") (class "Default")
      (node (ref "BC547-7") (pin "3") (pinfunction "E_3") (pintype "passive"))
      (node (ref "BC547-8") (pin "1") (pinfunction "C_1") (pintype "passive"))
    )
    (net (code "27") (name "Net-(BC547-8-B)") (class "Default")
      (node (ref "BC547-8") (pin "2") (pinfunction "B_2") (pintype "passive"))
      (node (ref "R22") (pin "2") (pinfunction "2_2") (pintype "passive"))
    )
    (net (code "28") (name "Net-(BC547-9-B)") (class "Default")
      (node (ref "BC547-9") (pin "2") (pinfunction "B_2") (pintype "passive"))
      (node (ref "R23") (pin "2") (pinfunction "2_2") (pintype "passive"))
    )
    (net (code "29") (name "Net-(BC547-10-B)") (class "Default")
      (node (ref "BC547-10") (pin "2") (pinfunction "B_2") (pintype "passive"))
      (node (ref "R24") (pin "2") (pinfunction "2_2") (pintype "passive"))
    )
    (net (code "30") (name "Net-(BC547-10-C)") (class "Default")
      (node (ref "BC547-10") (pin "1") (pinfunction "C_1") (pintype "passive"))
      (node (ref "BC547-9") (pin "1") (pinfunction "C_1") (pintype "passive"))
      (node (ref "NOR1") (pin "1") (pinfunction "A_1") (pintype "passive"))
      (node (ref "NORR1") (pin "2") (pinfunction "2_2") (pintype "passive"))
    )
    (net (code "31") (name "Net-(BC557-1-B)") (class "Default")
      (node (ref "BC557-1") (pin "2") (pinfunction "B_2") (pintype "passive"))
      (node (ref "R5") (pin "2") (pinfunction "2_2") (pintype "passive"))
    )
    (net (code "32") (name "Net-(BC557-1-E)") (class "Default")
      (node (ref "BC557-1") (pin "3") (pinfunction "E_3") (pintype "passive"))
      (node (ref "BUF2") (pin "1") (pinfunction "A_1") (pintype "passive"))
      (node (ref "BUFR2") (pin "2") (pinfunction "2_2") (pintype "passive"))
    )
    (net (code "33") (name "Net-(BC557-2-B)") (class "Default")
      (node (ref "BC557-2") (pin "2") (pinfunction "B_2") (pintype "passive"))
      (node (ref "R6") (pin "2") (pinfunction "2_2") (pintype "passive"))
    )
    (net (code "34") (name "Net-(BC557-2-C)") (class "Default")
      (node (ref "BC557-2") (pin "1") (pinfunction "C_1") (pintype "passive"))
      (node (ref "NOTR2") (pin "1") (pinfunction "1_1") (pintype "passive"))
    )
    (net (code "35") (name "Net-(BC557-3-B)") (class "Default")
      (node (ref "BC557-3") (pin "2") (pinfunction "B_2") (pintype "passive"))
      (node (ref "R7") (pin "2") (pinfunction "2_2") (pintype "passive"))
    )
    (net (code "36") (name "Net-(BC557-4-B)") (class "Default")
      (node (ref "BC557-4") (pin "2") (pinfunction "B_2") (pintype "passive"))
      (node (ref "R8") (pin "2") (pinfunction "2_2") (pintype "passive"))
    )
    (net (code "37") (name "Net-(BC557-5-B)") (class "Default")
      (node (ref "BC557-5") (pin "2") (pinfunction "B_2") (pintype "passive"))
      (node (ref "R9") (pin "2") (pinfunction "2_2") (pintype "passive"))
    )
    (net (code "38") (name "Net-(BC557-5-C)") (class "Default")
      (node (ref "BC557-5") (pin "1") (pinfunction "C_1") (pintype "passive"))
      (node (ref "BC557-6") (pin "3") (pinfunction "E_3") (pintype "passive"))
    )
    (net (code "39") (name "Net-(BC557-5-E)") (class "Default")
      (node (ref "BC557-5") (pin "3") (pinfunction "E_3") (pintype "passive"))
      (node (ref "OR2") (pin "1") (pinfunction "A_1") (pintype "passive"))
      (node (ref "ORR2") (pin "2") (pinfunction "2_2") (pintype "passive"))
    )
    (net (code "40") (name "Net-(BC557-6-B)") (class "Default")
      (node (ref "BC557-6") (pin "2") (pinfunction "B_2") (pintype "passive"))
      (node (ref "R10") (pin "2") (pinfunction "2_2") (pintype "passive"))
    )
    (net (code "41") (name "Net-(BC557-7-B)") (class "Default")
      (node (ref "BC557-7") (pin "2") (pinfunction "B_2") (pintype "passive"))
      (node (ref "R11") (pin "2") (pinfunction "2_2") (pintype "passive"))
    )
    (net (code "42") (name "Net-(BC557-7-C)") (class "Default")
      (node (ref "BC557-7") (pin "1") (pinfunction "C_1") (pintype "passive"))
      (node (ref "BC557-8") (pin "1") (pinfunction "C_1") (pintype "passive"))
      (node (ref "NANDR2") (pin "1") (pinfunction "1_1") (pintype "passive"))
    )
    (net (code "43") (name "Net-(BC557-8-B)") (class "Default")
      (node (ref "BC557-8") (pin "2") (pinfunction "B_2") (pintype "passive"))
      (node (ref "R12") (pin "2") (pinfunction "2_2") (pintype "passive"))
    )
    (net (code "44") (name "Net-(BC557-9-B)") (class "Default")
      (node (ref "BC557-9") (pin "2") (pinfunction "B_2") (pintype "passive"))
      (node (ref "R13") (pin "2") (pinfunction "2_2") (pintype "passive"))
    )
    (net (code "45") (name "Net-(BC557-10-B)") (class "Default")
      (node (ref "BC557-10") (pin "2") (pinfunction "B_2") (pintype "passive"))
      (node (ref "R14") (pin "2") (pinfunction "2_2") (pintype "passive"))
    )
    (net (code "46") (name "Net-(BC557-10-C)") (class "Default")
      (node (ref "BC557-10") (pin "1") (pinfunction "C_1") (pintype "passive"))
      (node (ref "NORR2") (pin "1") (pinfunction "1_1") (pintype "passive"))
    )
    (net (code "47") (name "Net-(BC557-10-E)") (class "Default")
      (node (ref "BC557-10") (pin "3") (pinfunction "E_3") (pintype "passive"))
      (node (ref "BC557-9") (pin "1") (pinfunction "C_1") (pintype "passive"))
    )
    (net (code "48") (name "Net-(BUF1-A)") (class "Default")
      (node (ref "BUF1") (pin "1") (pinfunction "A_1") (pintype "passive"))
      (node (ref "BUFR1") (pin "2") (pinfunction "2_2") (pintype "passive"))
    )
    (net (code "49") (name "Net-(LED-1-A)") (class "Default")
      (node (ref "LED-1") (pin "1") (pinfunction "A_1") (pintype "passive"))
      (node (ref "R1") (pin "2") (pinfunction "2_2") (pintype "passive"))
    )
    (net (code "50") (name "Net-(LED-2-A)") (class "Default")
      (node (ref "LED-2") (pin "1") (pinfunction "A_1") (pintype "passive"))
      (node (ref "R2") (pin "2") (pinfunction "2_2") (pintype "passive"))
    )
    (net (code "51") (name "Net-(LED-3-A)") (class "Default")
      (node (ref "LED-3") (pin "1") (pinfunction "A_1") (pintype "passive"))
      (node (ref "R3") (pin "2") (pinfunction "2_2") (pintype "passive"))
    )
    (net (code "52") (name "Net-(LED-4-A)") (class "Default")
      (node (ref "LED-4") (pin "1") (pinfunction "A_1") (pintype "passive"))
      (node (ref "R4") (pin "2") (pinfunction "2_2") (pintype "passive"))
    )
    (net (code "53") (name "Net-(NAND2-A)") (class "Default")
      (node (ref "NAND2") (pin "1") (pinfunction "A_1") (pintype "passive"))
      (node (ref "NANDR2") (pin "2") (pinfunction "2_2") (pintype "passive"))
    )
    (net (code "54") (name "Net-(NOR2-A)") (class "Default")
      (node (ref "NOR2") (pin "1") (pinfunction "A_1") (pintype "passive"))
      (node (ref "NORR2") (pin "2") (pinfunction "2_2") (pintype "passive"))
    )
    (net (code "55") (name "Net-(NOT2-A)") (class "Default")
      (node (ref "NOT2") (pin "1") (pinfunction "A_1") (pintype "passive"))
      (node (ref "NOTR2") (pin "2") (pinfunction "2_2") (pintype "passive"))
    )
    (net (code "56") (name "Net-(OR1-A)") (class "Default")
      (node (ref "OR1") (pin "1") (pinfunction "A_1") (pintype "passive"))
      (node (ref "ORR1") (pin "2") (pinfunction "2_2") (pintype "passive"))
    )
  )
)
